# WL-GENERATOR.net
KiCad netlist of a schematic drawn in Altium Designer
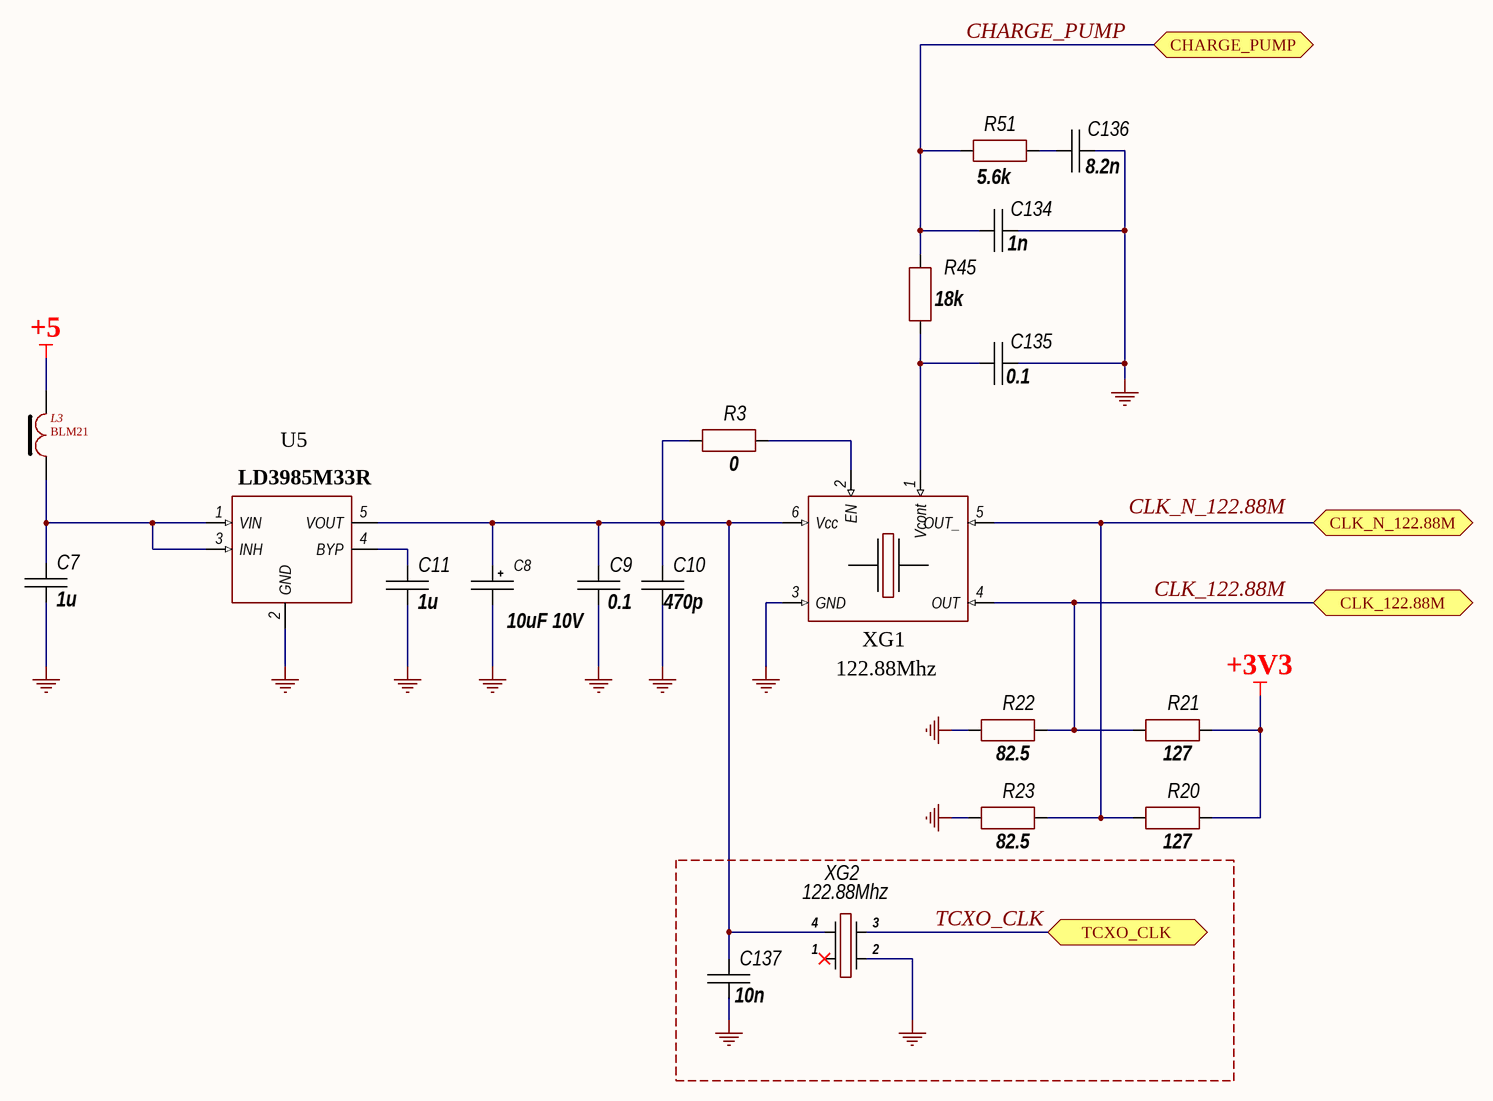
[diagram p0: WL-GENERATOR.SchDoc]

(export (version "E")
  (design (tool "Eeschema 10.0.6"))
  (components
    (comp (ref "C7")
      (value "1u")
      (footprint "standard:CH0805C")
      (libsource (lib "Discrete") (part "Capacitor"))
    )
    (comp (ref "C8")
      (value "10uF 10V")
      (footprint "standard:TANTAL_B")
      (libsource (lib "Discrete") (part "TantalCap"))
    )
    (comp (ref "C9")
      (value "0.1")
      (footprint "standard:CH0805C")
      (libsource (lib "Discrete") (part "Capacitor"))
    )
    (comp (ref "C10")
      (value "470p")
      (footprint "standard:CH0805C")
      (libsource (lib "Discrete") (part "Capacitor"))
    )
    (comp (ref "C11")
      (value "1u")
      (footprint "standard:CH0805C")
      (libsource (lib "Discrete") (part "Capacitor"))
    )
    (comp (ref "C134") (value "1n") (footprint "standard:CH0805C") (libsource (lib "") (part "Capacitor_1")))
    (comp (ref "C135") (value "0.1") (footprint "standard:CH0805C") (libsource (lib "") (part "Capacitor_1")))
    (comp (ref "C136")
      (value "8.2n")
      (footprint "standard:CH0805C")
      (libsource (lib "Discrete") (part "Capacitor"))
    )
    (comp (ref "C137")
      (value "10n")
      (footprint "standard:CH0805C")
      (libsource (lib "Discrete") (part "Capacitor"))
    )
    (comp (ref "L3") (value "BLM21") (footprint "CH0805L") (libsource (lib "Discrete") (part "FB-1")))
    (comp (ref "R3")
      (value "0")
      (footprint "standard:CH0805R")
      (libsource (lib "Discrete") (part "Resistor"))
    )
    (comp (ref "R20")
      (value "127")
      (footprint "standard:CH0805R")
      (libsource (lib "Discrete") (part "Resistor"))
    )
    (comp (ref "R21")
      (value "127")
      (footprint "standard:CH0805R")
      (libsource (lib "Discrete") (part "Resistor"))
    )
    (comp (ref "R22")
      (value "82.5")
      (footprint "standard:CH0805R")
      (libsource (lib "Discrete") (part "Resistor"))
    )
    (comp (ref "R23")
      (value "82.5")
      (footprint "standard:CH0805R")
      (libsource (lib "Discrete") (part "Resistor"))
    )
    (comp (ref "R45") (value "18k") (footprint "standard:CH0805R") (libsource (lib "") (part "Resistor_1")))
    (comp (ref "R51") (value "5.6k") (footprint "standard:CH0805R") (libsource (lib "") (part "Resistor_2")))
    (comp (ref "U5")
      (value "LD3985M33R")
      (footprint "SOT23-5")
      (libsource (lib "Digital") (part "LD3985M33R_SOT23"))
    )
    (comp (ref "XG1") (value "122.88Mhz") (libsource (lib "Digital") (part "Generator")))
    (comp (ref "XG2")
      (value "122.88Mhz")
      (footprint "custom:OSC: 5070")
      (libsource (lib "Discrete") (part "Generator"))
    )
  )
  (nets
    (net (code "1") (name "+3V3") (class "Default")
      (node (ref "R20") (pin "1") (pinfunction "1_1") (pintype "passive"))
      (node (ref "R21") (pin "1") (pinfunction "1_1") (pintype "passive"))
    )
    (net (code "2") (name "+5") (class "Default")
      (node (ref "L3") (pin "1") (pinfunction "1_1") (pintype "passive"))
    )
    (net (code "3") (name "/CHARGE_PUMP") (class "Default")
      (node (ref "C134") (pin "1") (pinfunction "1_1") (pintype "power_in"))
      (node (ref "R45") (pin "1") (pinfunction "1_1") (pintype "passive"))
      (node (ref "R51") (pin "1") (pinfunction "1_1") (pintype "passive"))
    )
    (net (code "4") (name "/CLK_122.88M") (class "Default")
      (node (ref "R21") (pin "2") (pinfunction "2_2") (pintype "passive"))
      (node (ref "R22") (pin "1") (pinfunction "1_1") (pintype "passive"))
      (node (ref "XG1") (pin "4") (pinfunction "OUT_4") (pintype "input"))
    )
    (net (code "5") (name "/CLK_N_122.88M") (class "Default")
      (node (ref "R20") (pin "2") (pinfunction "2_2") (pintype "passive"))
      (node (ref "R23") (pin "1") (pinfunction "1_1") (pintype "passive"))
      (node (ref "XG1") (pin "5") (pinfunction "OUT__5") (pintype "input"))
    )
    (net (code "6") (name "/TCXO_CLK") (class "Default")
      (node (ref "XG2") (pin "3") (pinfunction "3_3") (pintype "passive"))
    )
    (net (code "7") (name "GND") (class "Default")
      (node (ref "C10") (pin "2") (pinfunction "2_2") (pintype "power_in"))
      (node (ref "C11") (pin "2") (pinfunction "2_2") (pintype "power_in"))
      (node (ref "C134") (pin "2") (pinfunction "2_2") (pintype "power_in"))
      (node (ref "C135") (pin "2") (pinfunction "2_2") (pintype "power_in"))
      (node (ref "C136") (pin "2") (pinfunction "2_2") (pintype "power_in"))
      (node (ref "C137") (pin "2") (pinfunction "2_2") (pintype "power_in"))
      (node (ref "C7") (pin "2") (pinfunction "2_2") (pintype "power_in"))
      (node (ref "C8") (pin "2") (pinfunction "2_2") (pintype "power_in"))
      (node (ref "C9") (pin "2") (pinfunction "2_2") (pintype "power_in"))
      (node (ref "R22") (pin "2") (pinfunction "2_2") (pintype "passive"))
      (node (ref "R23") (pin "2") (pinfunction "2_2") (pintype "passive"))
      (node (ref "U5") (pin "2") (pinfunction "GND_2") (pintype "passive"))
      (node (ref "XG1") (pin "3") (pinfunction "GND_3") (pintype "input"))
      (node (ref "XG2") (pin "2") (pinfunction "2_2") (pintype "passive"))
    )
    (net (code "8") (name "Net-(C136-Pad1)") (class "Default")
      (node (ref "C136") (pin "1") (pinfunction "1_1") (pintype "power_in"))
      (node (ref "R51") (pin "2") (pinfunction "2_2") (pintype "passive"))
    )
    (net (code "9") (name "Net-(U5-BYP)") (class "Default")
      (node (ref "C11") (pin "1") (pinfunction "1_1") (pintype "power_in"))
      (node (ref "U5") (pin "4") (pinfunction "BYP_4") (pintype "passive"))
    )
    (net (code "10") (name "Net-(U5-INH)") (class "Default")
      (node (ref "C7") (pin "1") (pinfunction "1_1") (pintype "power_in"))
      (node (ref "L3") (pin "2") (pinfunction "2_2") (pintype "passive"))
      (node (ref "U5") (pin "1") (pinfunction "VIN_1") (pintype "input"))
      (node (ref "U5") (pin "3") (pinfunction "INH_3") (pintype "input"))
    )
    (net (code "11") (name "Net-(U5-VOUT)") (class "Default")
      (node (ref "C10") (pin "1") (pinfunction "1_1") (pintype "power_in"))
      (node (ref "C137") (pin "1") (pinfunction "1_1") (pintype "power_in"))
      (node (ref "C8") (pin "1") (pinfunction "1_1") (pintype "power_in"))
      (node (ref "C9") (pin "1") (pinfunction "1_1") (pintype "power_in"))
      (node (ref "R3") (pin "2") (pinfunction "2_2") (pintype "passive"))
      (node (ref "U5") (pin "5") (pinfunction "VOUT_5") (pintype "passive"))
      (node (ref "XG1") (pin "6") (pinfunction "Vcc_6") (pintype "input"))
      (node (ref "XG2") (pin "4") (pinfunction "4_4") (pintype "passive"))
    )
    (net (code "12") (name "Net-(XG1-EN)") (class "Default")
      (node (ref "R3") (pin "1") (pinfunction "1_1") (pintype "passive"))
      (node (ref "XG1") (pin "2") (pinfunction "EN_2") (pintype "input"))
    )
    (net (code "13") (name "Net-(XG1-Vcont)") (class "Default")
      (node (ref "C135") (pin "1") (pinfunction "1_1") (pintype "power_in"))
      (node (ref "R45") (pin "2") (pinfunction "2_2") (pintype "passive"))
      (node (ref "XG1") (pin "1") (pinfunction "Vcont_1") (pintype "input"))
    )
    (net (code "14") (name "unconnected-(XG2-Pad1)") (class "Default")
      (node (ref "XG2") (pin "1") (pinfunction "1_1") (pintype "passive+no_connect"))
    )
  )
)
